# wemos_D1.net
KiCad netlist of a schematic drawn in EAGLE
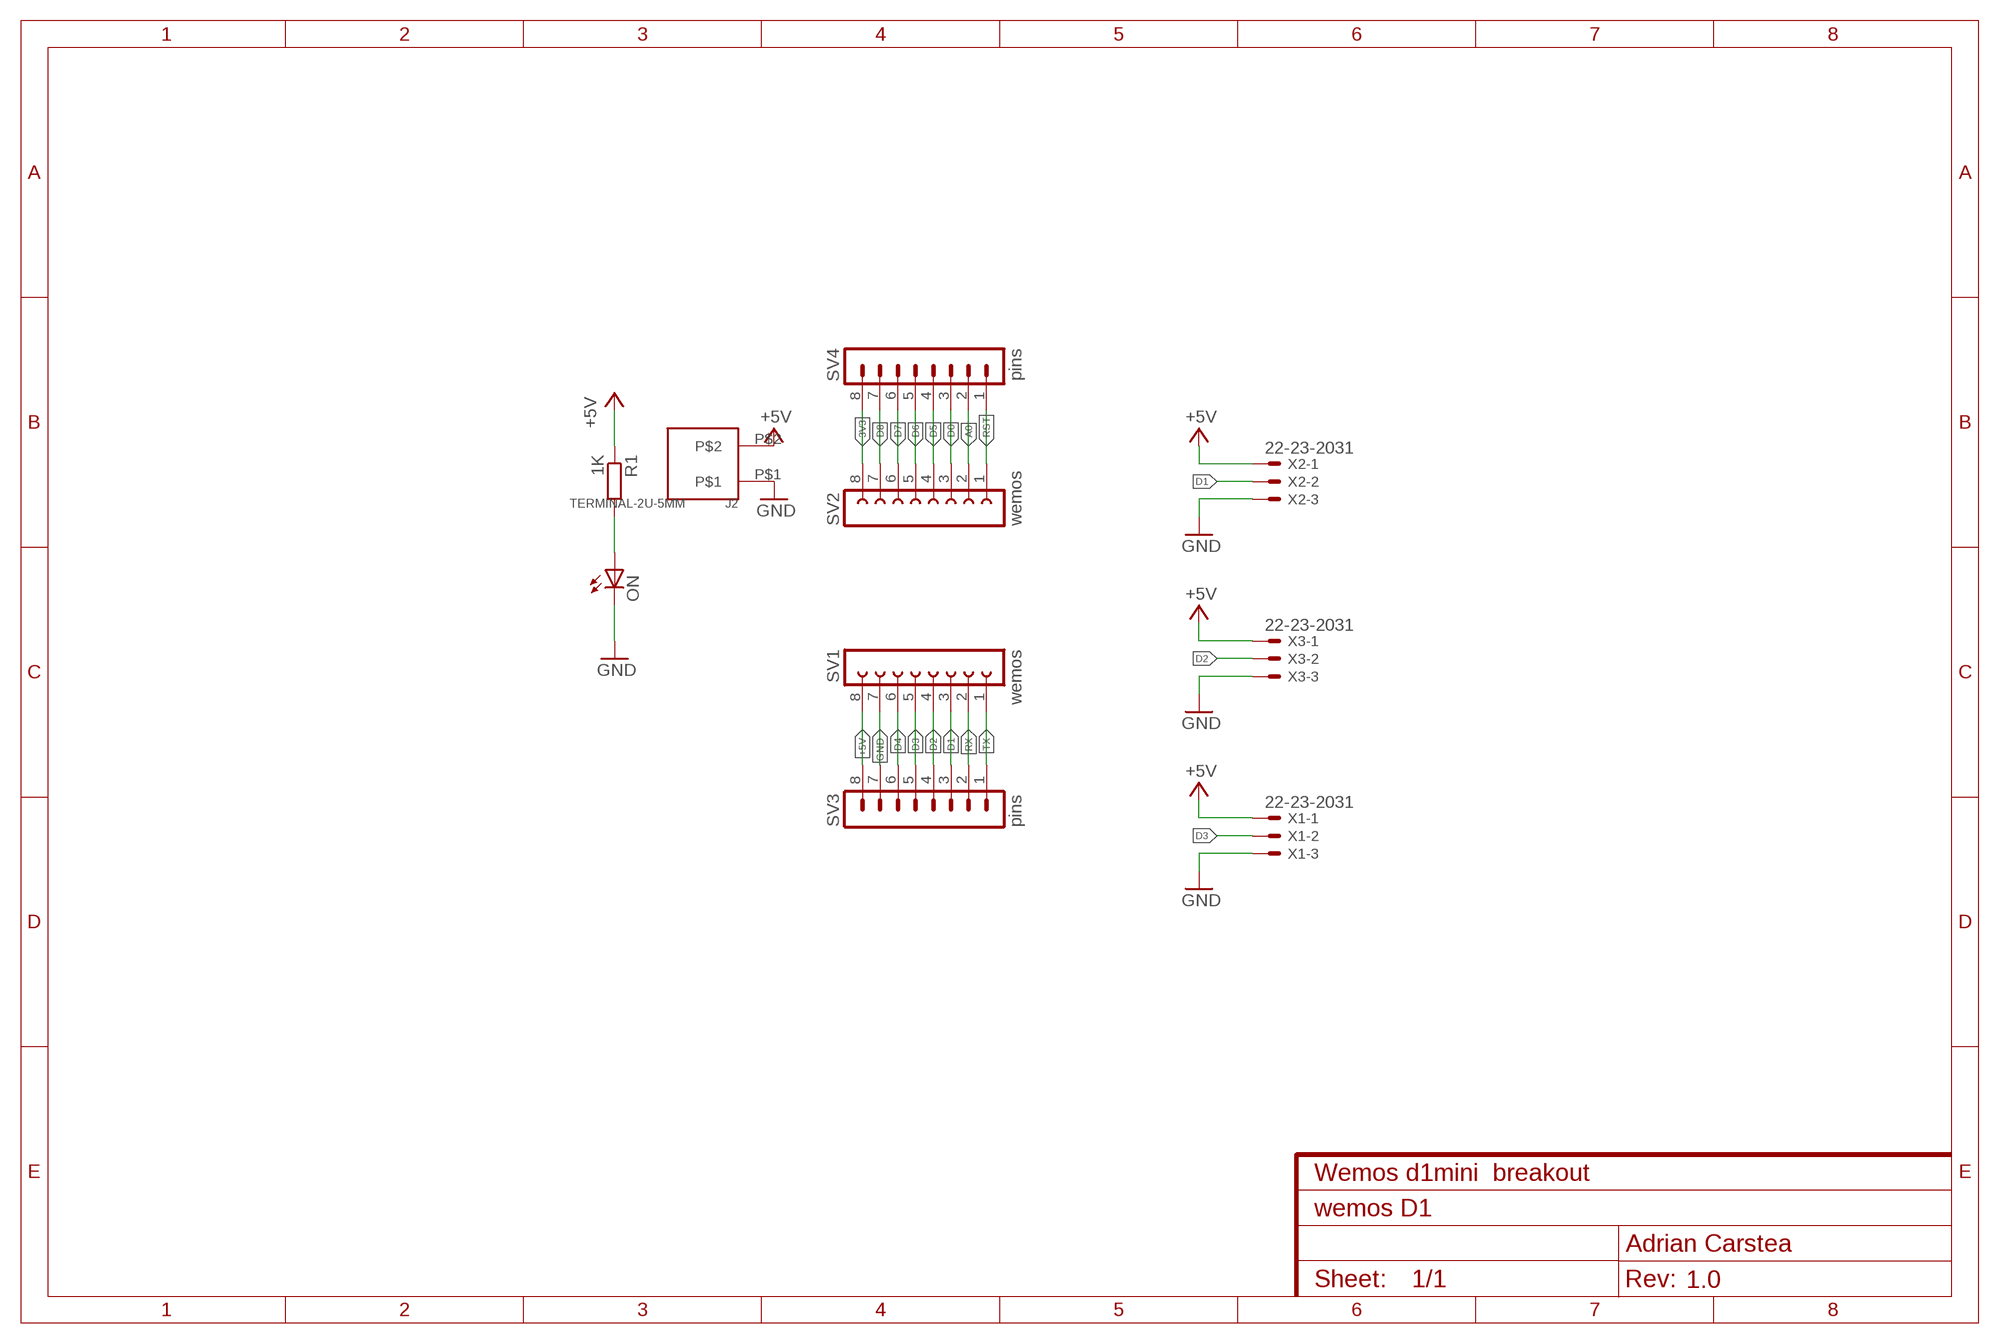
[diagram p0: schematic, sheet 1]

(export (version "E")
  (design (tool "Eeschema 10.0.6"))
  (components
    (comp (ref "1K")
      (value "R1")
      (footprint "eagle-import:R0805")
      (libsource (lib "eagle-import") (part "R-EU_R0805"))
    )
    (comp (ref "J2")
      (value "TERMINAL-2U-5MM")
      (footprint "eagle-import:TERMINAL-2U-5MM")
      (libsource (lib "eagle-import") (part "TERMINAL-2U-5MM"))
    )
    (comp (ref "ON")
      (value "LEDSML0805")
      (footprint "eagle-import:SML0805")
      (libsource (lib "eagle-import") (part "LEDSML0805"))
    )
    (comp (ref "SV1")
      (value "wemos")
      (footprint "eagle-import:FE08")
      (libsource (lib "eagle-import") (part "FE08-1"))
    )
    (comp (ref "SV2")
      (value "wemos")
      (footprint "eagle-import:FE08")
      (libsource (lib "eagle-import") (part "FE08-1"))
    )
    (comp (ref "SV3")
      (value "pins")
      (footprint "eagle-import:MA08-1")
      (libsource (lib "eagle-import") (part "MA08-1"))
    )
    (comp (ref "SV4")
      (value "pins")
      (footprint "eagle-import:MA08-1")
      (libsource (lib "eagle-import") (part "MA08-1"))
    )
    (comp (ref "X1")
      (value "22-23-2031")
      (footprint "eagle-import:22-23-2031")
      (fields (field (name "MF") "MOLEX"))
      (libsource (lib "eagle-import") (part "22-23-2031"))
    )
    (comp (ref "X2")
      (value "22-23-2031")
      (footprint "eagle-import:22-23-2031")
      (fields (field (name "MF") "MOLEX"))
      (libsource (lib "eagle-import") (part "22-23-2031"))
    )
    (comp (ref "X3")
      (value "22-23-2031")
      (footprint "eagle-import:22-23-2031")
      (fields (field (name "MF") "MOLEX"))
      (libsource (lib "eagle-import") (part "22-23-2031"))
    )
  )
  (nets
    (net (code "1") (name "+5V") (class "Default")
      (node (ref "1K") (pin "1") (pinfunction "1_1") (pintype "passive"))
      (node (ref "J2") (pin "P$2") (pinfunction "P$2_P$2") (pintype "bidirectional"))
      (node (ref "SV1") (pin "8") (pinfunction "8_8") (pintype "passive"))
      (node (ref "SV3") (pin "8") (pinfunction "8_8") (pintype "passive"))
      (node (ref "X1") (pin "1") (pinfunction "S_1") (pintype "passive"))
      (node (ref "X2") (pin "1") (pinfunction "S_1") (pintype "passive"))
      (node (ref "X3") (pin "1") (pinfunction "S_1") (pintype "passive"))
    )
    (net (code "2") (name "3V3") (class "Default")
      (node (ref "SV2") (pin "8") (pinfunction "8_8") (pintype "passive"))
      (node (ref "SV4") (pin "8") (pinfunction "8_8") (pintype "passive"))
    )
    (net (code "3") (name "A0") (class "Default")
      (node (ref "SV2") (pin "2") (pinfunction "2_2") (pintype "passive"))
      (node (ref "SV4") (pin "2") (pinfunction "2_2") (pintype "passive"))
    )
    (net (code "4") (name "D0") (class "Default")
      (node (ref "SV2") (pin "3") (pinfunction "3_3") (pintype "passive"))
      (node (ref "SV4") (pin "3") (pinfunction "3_3") (pintype "passive"))
    )
    (net (code "5") (name "D1") (class "Default")
      (node (ref "SV1") (pin "3") (pinfunction "3_3") (pintype "passive"))
      (node (ref "SV3") (pin "3") (pinfunction "3_3") (pintype "passive"))
      (node (ref "X2") (pin "2") (pinfunction "S_2") (pintype "passive"))
    )
    (net (code "6") (name "D2") (class "Default")
      (node (ref "SV1") (pin "4") (pinfunction "4_4") (pintype "passive"))
      (node (ref "SV3") (pin "4") (pinfunction "4_4") (pintype "passive"))
      (node (ref "X3") (pin "2") (pinfunction "S_2") (pintype "passive"))
    )
    (net (code "7") (name "D3") (class "Default")
      (node (ref "SV1") (pin "5") (pinfunction "5_5") (pintype "passive"))
      (node (ref "SV3") (pin "5") (pinfunction "5_5") (pintype "passive"))
      (node (ref "X1") (pin "2") (pinfunction "S_2") (pintype "passive"))
    )
    (net (code "8") (name "D4") (class "Default")
      (node (ref "SV1") (pin "6") (pinfunction "6_6") (pintype "passive"))
      (node (ref "SV3") (pin "6") (pinfunction "6_6") (pintype "passive"))
    )
    (net (code "9") (name "D5") (class "Default")
      (node (ref "SV2") (pin "4") (pinfunction "4_4") (pintype "passive"))
      (node (ref "SV4") (pin "4") (pinfunction "4_4") (pintype "passive"))
    )
    (net (code "10") (name "D6") (class "Default")
      (node (ref "SV2") (pin "5") (pinfunction "5_5") (pintype "passive"))
      (node (ref "SV4") (pin "5") (pinfunction "5_5") (pintype "passive"))
    )
    (net (code "11") (name "D7") (class "Default")
      (node (ref "SV2") (pin "6") (pinfunction "6_6") (pintype "passive"))
      (node (ref "SV4") (pin "6") (pinfunction "6_6") (pintype "passive"))
    )
    (net (code "12") (name "D8") (class "Default")
      (node (ref "SV2") (pin "7") (pinfunction "7_7") (pintype "passive"))
      (node (ref "SV4") (pin "7") (pinfunction "7_7") (pintype "passive"))
    )
    (net (code "13") (name "GND") (class "Default")
      (node (ref "J2") (pin "P$1") (pinfunction "P$1_P$1") (pintype "bidirectional"))
      (node (ref "ON") (pin "C") (pinfunction "C_C") (pintype "passive"))
      (node (ref "SV1") (pin "7") (pinfunction "7_7") (pintype "passive"))
      (node (ref "SV3") (pin "7") (pinfunction "7_7") (pintype "passive"))
      (node (ref "X1") (pin "3") (pinfunction "S_3") (pintype "passive"))
      (node (ref "X2") (pin "3") (pinfunction "S_3") (pintype "passive"))
      (node (ref "X3") (pin "3") (pinfunction "S_3") (pintype "passive"))
    )
    (net (code "14") (name "Net-(1K-Pad2)") (class "Default")
      (node (ref "1K") (pin "2") (pinfunction "2_2") (pintype "passive"))
      (node (ref "ON") (pin "A") (pinfunction "A_A") (pintype "passive"))
    )
    (net (code "15") (name "RST") (class "Default")
      (node (ref "SV2") (pin "1") (pinfunction "1_1") (pintype "passive"))
      (node (ref "SV4") (pin "1") (pinfunction "1_1") (pintype "passive"))
    )
    (net (code "16") (name "RX") (class "Default")
      (node (ref "SV1") (pin "2") (pinfunction "2_2") (pintype "passive"))
      (node (ref "SV3") (pin "2") (pinfunction "2_2") (pintype "passive"))
    )
    (net (code "17") (name "TX") (class "Default")
      (node (ref "SV1") (pin "1") (pinfunction "1_1") (pintype "passive"))
      (node (ref "SV3") (pin "1") (pinfunction "1_1") (pintype "passive"))
    )
  )
)
